# Sheet1.net
KiCad netlist of a schematic drawn in Altium Designer
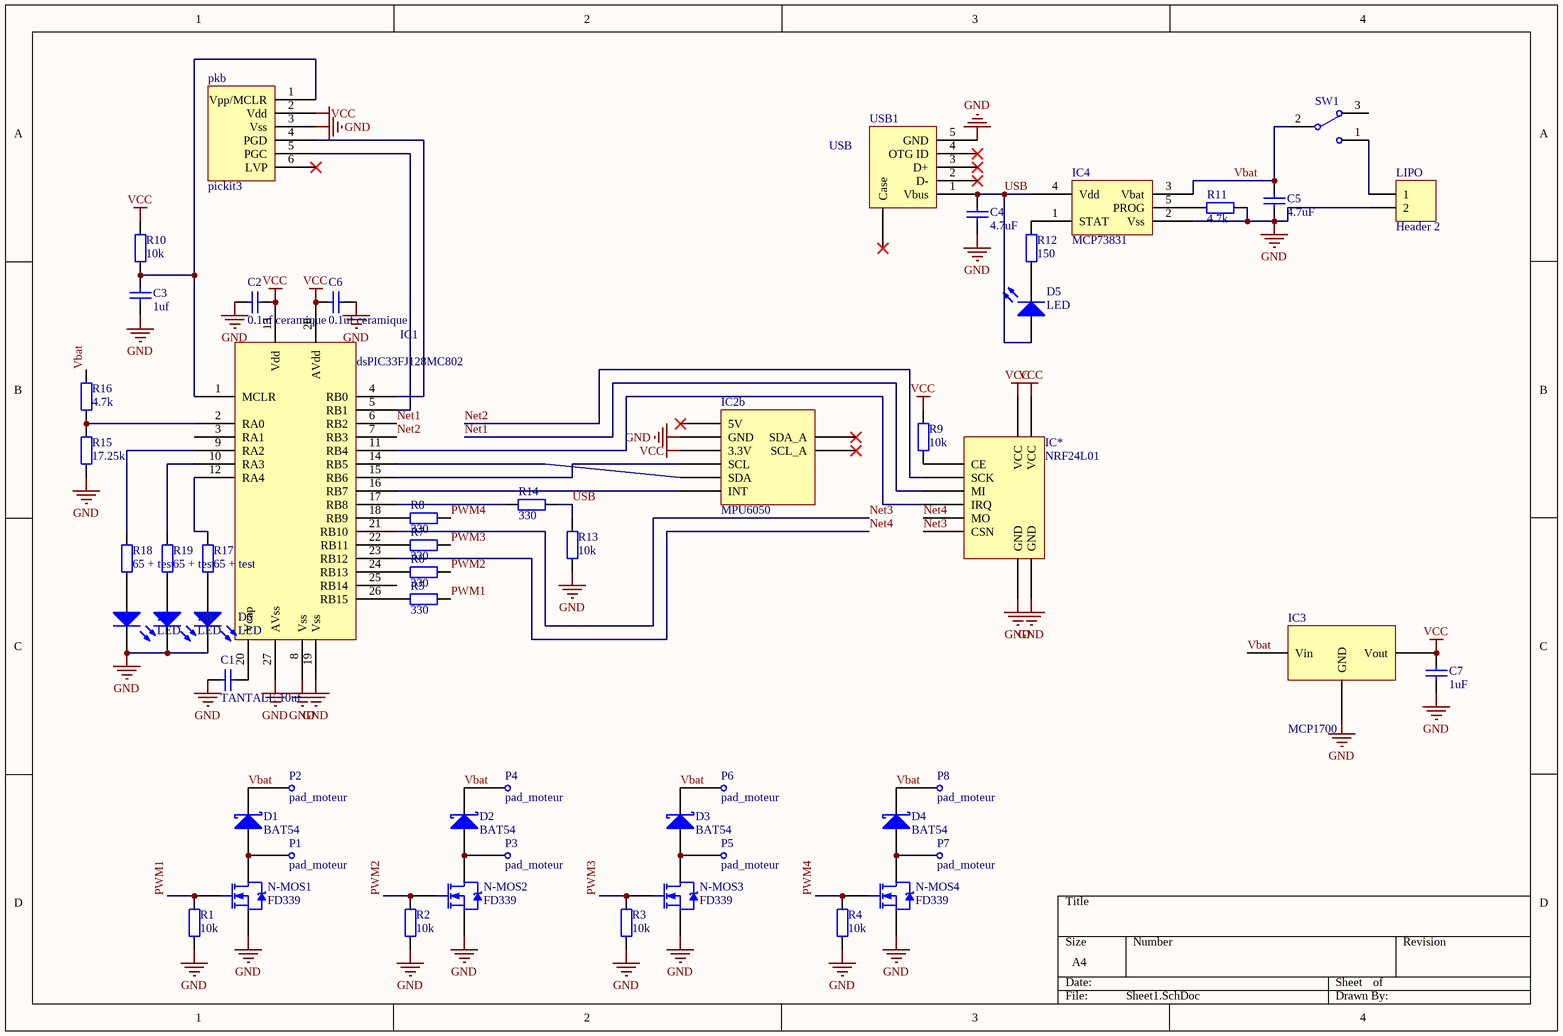
[diagram p0: Sheet1.SchDoc]

(export (version "E")
  (design (tool "Eeschema 10.0.6"))
  (components
    (comp (ref "C1")
      (value "TANTALE 10uf")
      (footprint "cms805")
      (libsource (lib "Integrated_Library1") (part "Capa"))
    )
    (comp (ref "C2")
      (value "0.1uf ceramique")
      (footprint "cms805")
      (libsource (lib "Integrated_Library1") (part "Capa"))
    )
    (comp (ref "C3") (value "1uf") (footprint "cms805") (libsource (lib "Integrated_Library1") (part "Capa")))
    (comp (ref "C4")
      (value "4.7uF")
      (footprint "cms805")
      (libsource (lib "Integrated_Library1") (part "Capa"))
    )
    (comp (ref "C5")
      (value "4.7uF")
      (footprint "cms805")
      (libsource (lib "Integrated_Library1") (part "Capa"))
    )
    (comp (ref "C6")
      (value "0.1uf ceramique")
      (footprint "cms805")
      (libsource (lib "Integrated_Library1") (part "Capa"))
    )
    (comp (ref "C7") (value "1uF") (footprint "cms805") (libsource (lib "Integrated_Library1") (part "Capa")))
    (comp (ref "D1")
      (value "BAT54")
      (footprint "SOT23")
      (libsource (lib "Integrated_Library1") (part "Schottky BAT54"))
    )
    (comp (ref "D2")
      (value "BAT54")
      (footprint "SOT23")
      (libsource (lib "Integrated_Library1") (part "Schottky BAT54"))
    )
    (comp (ref "D3")
      (value "BAT54")
      (footprint "SOT23")
      (libsource (lib "Integrated_Library1") (part "Schottky BAT54"))
    )
    (comp (ref "D4")
      (value "BAT54")
      (footprint "SOT23")
      (libsource (lib "Integrated_Library1") (part "Schottky BAT54"))
    )
    (comp (ref "D5") (value "LED") (footprint "cms1206") (libsource (lib "Integrated_Library1") (part "LED")))
    (comp (ref "D6") (value "LED") (footprint "cms1206") (libsource (lib "Integrated_Library1") (part "LED")))
    (comp (ref "D7") (value "LED") (footprint "cms1206") (libsource (lib "Integrated_Library1") (part "LED")))
    (comp (ref "D8") (value "LED") (footprint "cms1206") (libsource (lib "Integrated_Library1") (part "LED")))
    (comp (ref "IC*")
      (value "NRF24L01")
      (footprint "NRF24L01")
      (libsource (lib "Integrated_Library1") (part "NRF24L01"))
    )
    (comp (ref "IC1")
      (value "dsPIC33FJ128MC802")
      (footprint "SOIC28(300mil)")
      (libsource (lib "Integrated_Library1") (part "dsPIC33FJ128MC802"))
    )
    (comp (ref "IC2b")
      (value "MPU6050")
      (footprint "MPU6050_drotek")
      (libsource (lib "Integrated_Library1") (part "MPU6050-drotek"))
    )
    (comp (ref "IC3")
      (value "MCP1700")
      (footprint "SOT89")
      (libsource (lib "Integrated_Library1") (part "MCP1700"))
    )
    (comp (ref "IC4")
      (value "MCP73831")
      (footprint "SOT23-5")
      (libsource (lib "Integrated_Library1") (part "MCP73831 Li-Po"))
    )
    (comp (ref "LIPO")
      (value "Header 2")
      (footprint "HDR1X2")
      (description "Header, 2-Pin")
      (fields (field (name "PUBLISHER") "Altium Limited"))
      (libsource (lib "Miscellaneous Connectors") (part "Header 2"))
    )
    (comp (ref "N-MOS1")
      (value "FD339")
      (footprint "SOT23")
      (libsource (lib "Integrated_Library1") (part "N-MOS FD339"))
    )
    (comp (ref "N-MOS2")
      (value "FD339")
      (footprint "SOT23")
      (libsource (lib "Integrated_Library1") (part "N-MOS FD339"))
    )
    (comp (ref "N-MOS3")
      (value "FD339")
      (footprint "SOT23")
      (libsource (lib "Integrated_Library1") (part "N-MOS FD339"))
    )
    (comp (ref "N-MOS4")
      (value "FD339")
      (footprint "SOT23")
      (libsource (lib "Integrated_Library1") (part "N-MOS FD339"))
    )
    (comp (ref "P1")
      (value "pad_moteur")
      (footprint "PAD")
      (libsource (lib "Integrated_Library1") (part "pad_moteur"))
    )
    (comp (ref "P2")
      (value "pad_moteur")
      (footprint "PAD")
      (libsource (lib "Integrated_Library1") (part "pad_moteur"))
    )
    (comp (ref "P3")
      (value "pad_moteur")
      (footprint "PAD")
      (libsource (lib "Integrated_Library1") (part "pad_moteur"))
    )
    (comp (ref "P4")
      (value "pad_moteur")
      (footprint "PAD")
      (libsource (lib "Integrated_Library1") (part "pad_moteur"))
    )
    (comp (ref "P5")
      (value "pad_moteur")
      (footprint "PAD")
      (libsource (lib "Integrated_Library1") (part "pad_moteur"))
    )
    (comp (ref "P6")
      (value "pad_moteur")
      (footprint "PAD")
      (libsource (lib "Integrated_Library1") (part "pad_moteur"))
    )
    (comp (ref "P7")
      (value "pad_moteur")
      (footprint "PAD")
      (libsource (lib "Integrated_Library1") (part "pad_moteur"))
    )
    (comp (ref "P8")
      (value "pad_moteur")
      (footprint "PAD")
      (libsource (lib "Integrated_Library1") (part "pad_moteur"))
    )
    (comp (ref "pkb")
      (value "pickit3")
      (footprint "pickit3")
      (libsource (lib "Integrated_Library1") (part "pickit3"))
    )
    (comp (ref "R1")
      (value "10k")
      (footprint "cms805")
      (libsource (lib "Integrated_Library1") (part "Resistance"))
    )
    (comp (ref "R2")
      (value "10k")
      (footprint "cms805")
      (libsource (lib "Integrated_Library1") (part "Resistance"))
    )
    (comp (ref "R3")
      (value "10k")
      (footprint "cms805")
      (libsource (lib "Integrated_Library1") (part "Resistance"))
    )
    (comp (ref "R4")
      (value "10k")
      (footprint "cms805")
      (libsource (lib "Integrated_Library1") (part "Resistance"))
    )
    (comp (ref "R5") (value "330") (footprint "cms805") (libsource (lib "") (part "Resistance_1")))
    (comp (ref "R6") (value "330") (footprint "cms805") (libsource (lib "") (part "Resistance_1")))
    (comp (ref "R7") (value "330") (footprint "cms805") (libsource (lib "") (part "Resistance_1")))
    (comp (ref "R8") (value "330") (footprint "cms805") (libsource (lib "") (part "Resistance_1")))
    (comp (ref "R9")
      (value "10k")
      (footprint "cms805")
      (libsource (lib "Integrated_Library1") (part "Resistance"))
    )
    (comp (ref "R10")
      (value "10k")
      (footprint "cms805")
      (libsource (lib "Integrated_Library1") (part "Resistance"))
    )
    (comp (ref "R11") (value "4.7k") (footprint "cms805") (libsource (lib "") (part "Resistance_2")))
    (comp (ref "R12") (value "150") (footprint "cms805") (libsource (lib "") (part "Resistance_3")))
    (comp (ref "R13")
      (value "10k")
      (footprint "cms805")
      (libsource (lib "Integrated_Library1") (part "Resistance"))
    )
    (comp (ref "R14") (value "330") (footprint "cms805") (libsource (lib "") (part "Resistance_2")))
    (comp (ref "R15")
      (value "17.25k")
      (footprint "cms805")
      (libsource (lib "Integrated_Library1") (part "Resistance"))
    )
    (comp (ref "R16")
      (value "4.7k")
      (footprint "cms805")
      (libsource (lib "Integrated_Library1") (part "Resistance"))
    )
    (comp (ref "R17")
      (value "65 + test")
      (footprint "cms805")
      (libsource (lib "Integrated_Library1") (part "Resistance"))
    )
    (comp (ref "R18")
      (value "65 + test")
      (footprint "cms805")
      (libsource (lib "Integrated_Library1") (part "Resistance"))
    )
    (comp (ref "R19")
      (value "65 + test")
      (footprint "cms805")
      (libsource (lib "Integrated_Library1") (part "Resistance"))
    )
    (comp (ref "SW1")
      (value "~")
      (footprint "inverseur")
      (libsource (lib "Integrated_Library1") (part "switch"))
    )
    (comp (ref "USB1")
      (value "USB")
      (footprint "USB_con")
      (libsource (lib "Integrated_Library1") (part "USB"))
    )
  )
  (nets
    (net (code "1") (name "/Net1") (class "Default")
      (node (ref "IC*") (pin "4") (pinfunction "MI_4") (pintype "passive"))
      (node (ref "IC1") (pin "6") (pinfunction "RB2_6") (pintype "passive"))
    )
    (net (code "2") (name "/Net2") (class "Default")
      (node (ref "IC*") (pin "3") (pinfunction "SCK_3") (pintype "passive"))
      (node (ref "IC1") (pin "7") (pinfunction "RB3_7") (pintype "passive"))
    )
    (net (code "3") (name "/Net3") (class "Default")
      (node (ref "IC*") (pin "9") (pinfunction "CSN_9") (pintype "passive"))
      (node (ref "IC1") (pin "21") (pinfunction "RB10_21") (pintype "passive"))
    )
    (net (code "4") (name "/Net4") (class "Default")
      (node (ref "IC*") (pin "8") (pinfunction "MO_8") (pintype "passive"))
      (node (ref "IC1") (pin "23") (pinfunction "RB12_23") (pintype "passive"))
    )
    (net (code "5") (name "/PWM1") (class "Default")
      (node (ref "N-MOS1") (pin "1") (pinfunction "G_1") (pintype "passive"))
      (node (ref "R1") (pin "2") (pinfunction "2_2") (pintype "passive"))
      (node (ref "R5") (pin "2") (pinfunction "2_2") (pintype "passive"))
    )
    (net (code "6") (name "/PWM2") (class "Default")
      (node (ref "N-MOS2") (pin "1") (pinfunction "G_1") (pintype "passive"))
      (node (ref "R2") (pin "2") (pinfunction "2_2") (pintype "passive"))
      (node (ref "R6") (pin "2") (pinfunction "2_2") (pintype "passive"))
    )
    (net (code "7") (name "/PWM3") (class "Default")
      (node (ref "N-MOS3") (pin "1") (pinfunction "G_1") (pintype "passive"))
      (node (ref "R3") (pin "2") (pinfunction "2_2") (pintype "passive"))
      (node (ref "R7") (pin "2") (pinfunction "2_2") (pintype "passive"))
    )
    (net (code "8") (name "/PWM4") (class "Default")
      (node (ref "N-MOS4") (pin "1") (pinfunction "G_1") (pintype "passive"))
      (node (ref "R4") (pin "2") (pinfunction "2_2") (pintype "passive"))
      (node (ref "R8") (pin "2") (pinfunction "2_2") (pintype "passive"))
    )
    (net (code "9") (name "/USB") (class "Default")
      (node (ref "C4") (pin "2") (pinfunction "2_2") (pintype "passive"))
      (node (ref "D5") (pin "1") (pinfunction "A_1") (pintype "passive"))
      (node (ref "IC4") (pin "4") (pinfunction "Vdd_4") (pintype "passive"))
      (node (ref "R13") (pin "2") (pinfunction "2_2") (pintype "passive"))
      (node (ref "R14") (pin "1") (pinfunction "1_1") (pintype "passive"))
      (node (ref "USB1") (pin "1") (pinfunction "Vbus_1") (pintype "passive"))
    )
    (net (code "10") (name "/Vbat") (class "Default")
      (node (ref "C5") (pin "2") (pinfunction "2_2") (pintype "passive"))
      (node (ref "D1") (pin "2") (pinfunction "K_2") (pintype "passive"))
      (node (ref "D2") (pin "2") (pinfunction "K_2") (pintype "passive"))
      (node (ref "D3") (pin "2") (pinfunction "K_2") (pintype "passive"))
      (node (ref "D4") (pin "2") (pinfunction "K_2") (pintype "passive"))
      (node (ref "IC3") (pin "2") (pinfunction "Vin_2") (pintype "passive"))
      (node (ref "IC4") (pin "3") (pinfunction "Vbat_3") (pintype "passive"))
      (node (ref "P2") (pin "1") (pintype "passive"))
      (node (ref "P4") (pin "1") (pintype "passive"))
      (node (ref "P6") (pin "1") (pintype "passive"))
      (node (ref "P8") (pin "1") (pintype "passive"))
      (node (ref "R16") (pin "2") (pinfunction "2_2") (pintype "passive"))
      (node (ref "SW1") (pin "2") (pinfunction "2_2") (pintype "passive"))
    )
    (net (code "11") (name "GND") (class "Default")
      (node (ref "C1") (pin "1") (pinfunction "1_1") (pintype "passive"))
      (node (ref "C2") (pin "1") (pinfunction "1_1") (pintype "passive"))
      (node (ref "C3") (pin "1") (pinfunction "1_1") (pintype "passive"))
      (node (ref "C4") (pin "1") (pinfunction "1_1") (pintype "passive"))
      (node (ref "C5") (pin "1") (pinfunction "1_1") (pintype "passive"))
      (node (ref "C6") (pin "2") (pinfunction "2_2") (pintype "passive"))
      (node (ref "C7") (pin "1") (pinfunction "1_1") (pintype "passive"))
      (node (ref "D6") (pin "2") (pinfunction "K_2") (pintype "passive"))
      (node (ref "D7") (pin "2") (pinfunction "K_2") (pintype "passive"))
      (node (ref "D8") (pin "2") (pinfunction "K_2") (pintype "passive"))
      (node (ref "IC*") (pin "5") (pinfunction "GND_5") (pintype "passive"))
      (node (ref "IC*") (pin "6") (pinfunction "GND_6") (pintype "passive"))
      (node (ref "IC1") (pin "19") (pinfunction "Vss_19") (pintype "passive"))
      (node (ref "IC1") (pin "27") (pinfunction "AVss_27") (pintype "passive"))
      (node (ref "IC1") (pin "8") (pinfunction "Vss_8") (pintype "passive"))
      (node (ref "IC2b") (pin "2") (pinfunction "GND_2") (pintype "passive"))
      (node (ref "IC3") (pin "1") (pinfunction "GND_1") (pintype "passive"))
      (node (ref "IC4") (pin "2") (pinfunction "Vss_2") (pintype "passive"))
      (node (ref "LIPO") (pin "2") (pinfunction "2_2") (pintype "passive"))
      (node (ref "N-MOS1") (pin "3") (pinfunction "S_3") (pintype "passive"))
      (node (ref "N-MOS2") (pin "3") (pinfunction "S_3") (pintype "passive"))
      (node (ref "N-MOS3") (pin "3") (pinfunction "S_3") (pintype "passive"))
      (node (ref "N-MOS4") (pin "3") (pinfunction "S_3") (pintype "passive"))
      (node (ref "R1") (pin "1") (pinfunction "1_1") (pintype "passive"))
      (node (ref "R11") (pin "1") (pinfunction "1_1") (pintype "passive"))
      (node (ref "R13") (pin "1") (pinfunction "1_1") (pintype "passive"))
      (node (ref "R15") (pin "1") (pinfunction "1_1") (pintype "passive"))
      (node (ref "R2") (pin "1") (pinfunction "1_1") (pintype "passive"))
      (node (ref "R3") (pin "1") (pinfunction "1_1") (pintype "passive"))
      (node (ref "R4") (pin "1") (pinfunction "1_1") (pintype "passive"))
      (node (ref "USB1") (pin "5") (pinfunction "GND_5") (pintype "passive"))
      (node (ref "pkb") (pin "3") (pinfunction "Vss_3") (pintype "passive"))
    )
    (net (code "12") (name "Net-(D1-A)") (class "Default")
      (node (ref "D1") (pin "1") (pinfunction "A_1") (pintype "passive"))
      (node (ref "N-MOS1") (pin "2") (pinfunction "D_2") (pintype "passive"))
      (node (ref "P1") (pin "1") (pintype "passive"))
    )
    (net (code "13") (name "Net-(D2-A)") (class "Default")
      (node (ref "D2") (pin "1") (pinfunction "A_1") (pintype "passive"))
      (node (ref "N-MOS2") (pin "2") (pinfunction "D_2") (pintype "passive"))
      (node (ref "P3") (pin "1") (pintype "passive"))
    )
    (net (code "14") (name "Net-(D3-A)") (class "Default")
      (node (ref "D3") (pin "1") (pinfunction "A_1") (pintype "passive"))
      (node (ref "N-MOS3") (pin "2") (pinfunction "D_2") (pintype "passive"))
      (node (ref "P5") (pin "1") (pintype "passive"))
    )
    (net (code "15") (name "Net-(D4-A)") (class "Default")
      (node (ref "D4") (pin "1") (pinfunction "A_1") (pintype "passive"))
      (node (ref "N-MOS4") (pin "2") (pinfunction "D_2") (pintype "passive"))
      (node (ref "P7") (pin "1") (pintype "passive"))
    )
    (net (code "16") (name "Net-(D5-K)") (class "Default")
      (node (ref "D5") (pin "2") (pinfunction "K_2") (pintype "passive"))
      (node (ref "R12") (pin "2") (pinfunction "2_2") (pintype "passive"))
    )
    (net (code "17") (name "Net-(D6-A)") (class "Default")
      (node (ref "D6") (pin "1") (pinfunction "A_1") (pintype "passive"))
      (node (ref "R17") (pin "1") (pinfunction "1_1") (pintype "passive"))
    )
    (net (code "18") (name "Net-(D7-A)") (class "Default")
      (node (ref "D7") (pin "1") (pinfunction "A_1") (pintype "passive"))
      (node (ref "R18") (pin "1") (pinfunction "1_1") (pintype "passive"))
    )
    (net (code "19") (name "Net-(D8-A)") (class "Default")
      (node (ref "D8") (pin "1") (pinfunction "A_1") (pintype "passive"))
      (node (ref "R19") (pin "1") (pinfunction "1_1") (pintype "passive"))
    )
    (net (code "20") (name "Net-(IC*-CE)") (class "Default")
      (node (ref "IC*") (pin "2") (pinfunction "CE_2") (pintype "passive"))
      (node (ref "R9") (pin "1") (pinfunction "1_1") (pintype "passive"))
    )
    (net (code "21") (name "Net-(IC*-IRQ)") (class "Default")
      (node (ref "IC*") (pin "7") (pinfunction "IRQ_7") (pintype "passive"))
      (node (ref "IC1") (pin "11") (pinfunction "RB4_11") (pintype "passive"))
    )
    (net (code "22") (name "Net-(IC1-MCLR)") (class "Default")
      (node (ref "C3") (pin "2") (pinfunction "2_2") (pintype "passive"))
      (node (ref "IC1") (pin "1") (pinfunction "MCLR_1") (pintype "passive"))
      (node (ref "R10") (pin "1") (pinfunction "1_1") (pintype "passive"))
      (node (ref "pkb") (pin "1") (pinfunction "Vpp/MCLR_1") (pintype "passive"))
    )
    (net (code "23") (name "Net-(IC1-RA0)") (class "Default")
      (node (ref "IC1") (pin "2") (pinfunction "RA0_2") (pintype "passive"))
      (node (ref "R15") (pin "2") (pinfunction "2_2") (pintype "passive"))
      (node (ref "R16") (pin "1") (pinfunction "1_1") (pintype "passive"))
    )
    (net (code "24") (name "Net-(IC1-RA2)") (class "Default")
      (node (ref "IC1") (pin "9") (pinfunction "RA2_9") (pintype "passive"))
      (node (ref "R18") (pin "2") (pinfunction "2_2") (pintype "passive"))
    )
    (net (code "25") (name "Net-(IC1-RA3)") (class "Default")
      (node (ref "IC1") (pin "10") (pinfunction "RA3_10") (pintype "passive"))
      (node (ref "R19") (pin "2") (pinfunction "2_2") (pintype "passive"))
    )
    (net (code "26") (name "Net-(IC1-RA4)") (class "Default")
      (node (ref "IC1") (pin "12") (pinfunction "RA4_12") (pintype "passive"))
      (node (ref "R17") (pin "2") (pinfunction "2_2") (pintype "passive"))
    )
    (net (code "27") (name "Net-(IC1-RB0)") (class "Default")
      (node (ref "IC1") (pin "4") (pinfunction "RB0_4") (pintype "passive"))
      (node (ref "pkb") (pin "4") (pinfunction "PGD_4") (pintype "passive"))
    )
    (net (code "28") (name "Net-(IC1-RB1)") (class "Default")
      (node (ref "IC1") (pin "5") (pinfunction "RB1_5") (pintype "passive"))
      (node (ref "pkb") (pin "5") (pinfunction "PGC_5") (pintype "passive"))
    )
    (net (code "29") (name "Net-(IC1-RB5)") (class "Default")
      (node (ref "IC1") (pin "14") (pinfunction "RB5_14") (pintype "passive"))
      (node (ref "IC2b") (pin "5") (pinfunction "SDA_5") (pintype "passive"))
    )
    (net (code "30") (name "Net-(IC1-RB6)") (class "Default")
      (node (ref "IC1") (pin "15") (pinfunction "RB6_15") (pintype "passive"))
      (node (ref "IC2b") (pin "4") (pinfunction "SCL_4") (pintype "passive"))
    )
    (net (code "31") (name "Net-(IC1-RB7)") (class "Default")
      (node (ref "IC1") (pin "16") (pinfunction "RB7_16") (pintype "passive"))
      (node (ref "IC2b") (pin "6") (pinfunction "INT_6") (pintype "passive"))
    )
    (net (code "32") (name "Net-(IC1-RB8)") (class "Default")
      (node (ref "IC1") (pin "17") (pinfunction "RB8_17") (pintype "passive"))
      (node (ref "R14") (pin "2") (pinfunction "2_2") (pintype "passive"))
    )
    (net (code "33") (name "Net-(IC1-RB9)") (class "Default")
      (node (ref "IC1") (pin "18") (pinfunction "RB9_18") (pintype "passive"))
      (node (ref "R8") (pin "1") (pinfunction "1_1") (pintype "passive"))
    )
    (net (code "34") (name "Net-(IC1-RB11)") (class "Default")
      (node (ref "IC1") (pin "22") (pinfunction "RB11_22") (pintype "passive"))
      (node (ref "R7") (pin "1") (pinfunction "1_1") (pintype "passive"))
    )
    (net (code "35") (name "Net-(IC1-RB13)") (class "Default")
      (node (ref "IC1") (pin "24") (pinfunction "RB13_24") (pintype "passive"))
      (node (ref "R6") (pin "1") (pinfunction "1_1") (pintype "passive"))
    )
    (net (code "36") (name "Net-(IC1-RB15)") (class "Default")
      (node (ref "IC1") (pin "26") (pinfunction "RB15_26") (pintype "passive"))
      (node (ref "R5") (pin "1") (pinfunction "1_1") (pintype "passive"))
    )
    (net (code "37") (name "Net-(IC1-Vcap)") (class "Default")
      (node (ref "C1") (pin "2") (pinfunction "2_2") (pintype "passive"))
      (node (ref "IC1") (pin "20") (pinfunction "Vcap_20") (pintype "passive"))
    )
    (net (code "38") (name "Net-(IC4-PROG)") (class "Default")
      (node (ref "IC4") (pin "5") (pinfunction "PROG_5") (pintype "passive"))
      (node (ref "R11") (pin "2") (pinfunction "2_2") (pintype "passive"))
    )
    (net (code "39") (name "Net-(IC4-STAT)") (class "Default")
      (node (ref "IC4") (pin "1") (pinfunction "STAT_1") (pintype "passive"))
      (node (ref "R12") (pin "1") (pinfunction "1_1") (pintype "passive"))
    )
    (net (code "40") (name "Net-(LIPO-Pad1)") (class "Default")
      (node (ref "LIPO") (pin "1") (pinfunction "1_1") (pintype "passive"))
      (node (ref "SW1") (pin "1") (pinfunction "1_1") (pintype "passive"))
    )
    (net (code "41") (name "VCC") (class "Default")
      (node (ref "C2") (pin "2") (pinfunction "2_2") (pintype "passive"))
      (node (ref "C6") (pin "1") (pinfunction "1_1") (pintype "passive"))
      (node (ref "C7") (pin "2") (pinfunction "2_2") (pintype "passive"))
      (node (ref "IC*") (pin "1") (pinfunction "VCC_1") (pintype "passive"))
      (node (ref "IC*") (pin "10") (pinfunction "VCC_10") (pintype "passive"))
      (node (ref "IC1") (pin "13") (pinfunction "Vdd_13") (pintype "passive"))
      (node (ref "IC1") (pin "28") (pinfunction "AVdd_28") (pintype "passive"))
      (node (ref "IC2b") (pin "3") (pinfunction "3.3V_3") (pintype "passive"))
      (node (ref "IC3") (pin "3") (pinfunction "Vout_3") (pintype "passive"))
      (node (ref "R10") (pin "2") (pinfunction "2_2") (pintype "passive"))
      (node (ref "R9") (pin "2") (pinfunction "2_2") (pintype "passive"))
      (node (ref "pkb") (pin "2") (pinfunction "Vdd_2") (pintype "passive"))
    )
    (net (code "42") (name "unconnected-(IC1-RA1-Pad3)") (class "Default")
      (node (ref "IC1") (pin "3") (pinfunction "RA1_3") (pintype "passive"))
    )
    (net (code "43") (name "unconnected-(IC1-RB14-Pad25)") (class "Default")
      (node (ref "IC1") (pin "25") (pinfunction "RB14_25") (pintype "passive"))
    )
    (net (code "44") (name "unconnected-(IC2b-5V-Pad1)") (class "Default")
      (node (ref "IC2b") (pin "1") (pinfunction "5V_1") (pintype "passive+no_connect"))
    )
    (net (code "45") (name "unconnected-(IC2b-SCL_A-Pad8)") (class "Default")
      (node (ref "IC2b") (pin "8") (pinfunction "SCL_A_8") (pintype "passive+no_connect"))
    )
    (net (code "46") (name "unconnected-(IC2b-SDA_A-Pad7)") (class "Default")
      (node (ref "IC2b") (pin "7") (pinfunction "SDA_A_7") (pintype "passive+no_connect"))
    )
    (net (code "47") (name "unconnected-(SW1-Pad3)") (class "Default")
      (node (ref "SW1") (pin "3") (pinfunction "3_3") (pintype "passive"))
    )
    (net (code "48") (name "unconnected-(USB1-Case-Pad0)") (class "Default")
      (node (ref "USB1") (pin "0") (pinfunction "Case_0") (pintype "passive+no_connect"))
    )
    (net (code "49") (name "unconnected-(USB1-D+-Pad3)") (class "Default")
      (node (ref "USB1") (pin "3") (pinfunction "D+_3") (pintype "passive+no_connect"))
    )
    (net (code "50") (name "unconnected-(USB1-D--Pad2)") (class "Default")
      (node (ref "USB1") (pin "2") (pinfunction "D-_2") (pintype "passive+no_connect"))
    )
    (net (code "51") (name "unconnected-(USB1-OTG_ID-Pad4)") (class "Default")
      (node (ref "USB1") (pin "4") (pinfunction "OTG_ID_4") (pintype "passive+no_connect"))
    )
    (net (code "52") (name "unconnected-(pkb-LVP-Pad6)") (class "Default")
      (node (ref "pkb") (pin "6") (pinfunction "LVP_6") (pintype "passive+no_connect"))
    )
  )
)
